# tussenprint.net
KiCad netlist of a schematic drawn in Altium Designer
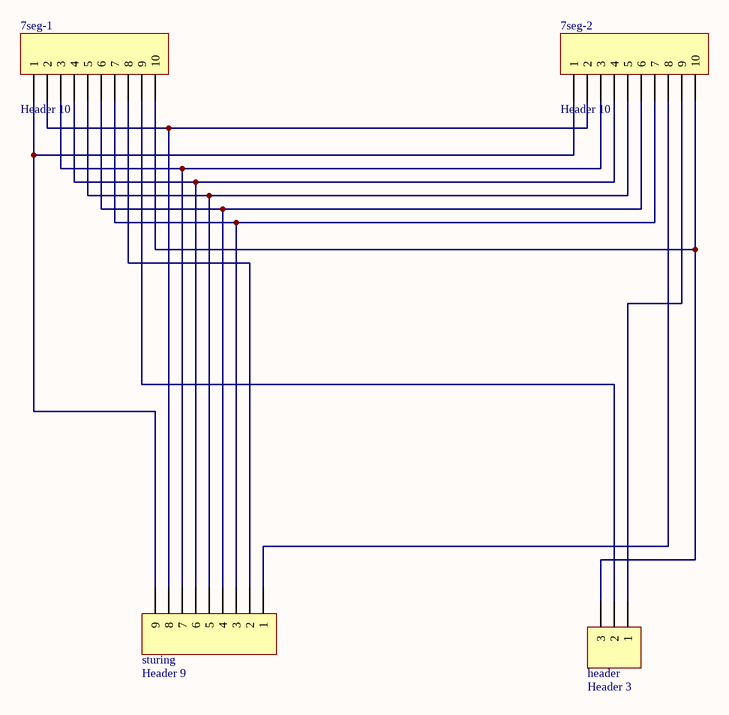
[diagram p0: tussenprint.SchDoc]

(export (version "E")
  (design (tool "Eeschema 10.0.6"))
  (components
    (comp (ref "7seg-1")
      (value "Header 10")
      (footprint "HDR1X10")
      (description "Header, 10-Pin")
      (fields (field (name "PUBLISHER") "Altium Limited"))
      (libsource (lib "Miscellaneous Connectors") (part "Header 10"))
    )
    (comp (ref "7seg-2")
      (value "Header 10")
      (footprint "HDR1X10")
      (description "Header, 10-Pin")
      (fields (field (name "PUBLISHER") "Altium Limited"))
      (libsource (lib "Miscellaneous Connectors") (part "Header 10"))
    )
    (comp (ref "header")
      (value "Header 3")
      (footprint "HDR1X3")
      (description "Header, 3-Pin")
      (fields (field (name "PUBLISHER") "Altium Limited"))
      (libsource (lib "Miscellaneous Connectors") (part "Header 3"))
    )
    (comp (ref "sturing")
      (value "Header 9")
      (footprint "HDR1X9")
      (description "Header, 9-Pin")
      (fields (field (name "PUBLISHER") "Altium Limited"))
      (libsource (lib "Miscellaneous Connectors") (part "Header 9"))
    )
  )
  (nets
    (net (code "1") (name "Net-(7seg-1-Pad1)") (class "Default")
      (node (ref "7seg-1") (pin "1") (pinfunction "1_1") (pintype "passive"))
      (node (ref "7seg-2") (pin "1") (pinfunction "1_1") (pintype "passive"))
      (node (ref "sturing") (pin "9") (pinfunction "9_9") (pintype "passive"))
    )
    (net (code "2") (name "Net-(7seg-1-Pad2)") (class "Default")
      (node (ref "7seg-1") (pin "2") (pinfunction "2_2") (pintype "passive"))
      (node (ref "7seg-2") (pin "2") (pinfunction "2_2") (pintype "passive"))
      (node (ref "sturing") (pin "8") (pinfunction "8_8") (pintype "passive"))
    )
    (net (code "3") (name "Net-(7seg-1-Pad3)") (class "Default")
      (node (ref "7seg-1") (pin "3") (pinfunction "3_3") (pintype "passive"))
      (node (ref "7seg-2") (pin "3") (pinfunction "3_3") (pintype "passive"))
      (node (ref "sturing") (pin "7") (pinfunction "7_7") (pintype "passive"))
    )
    (net (code "4") (name "Net-(7seg-1-Pad4)") (class "Default")
      (node (ref "7seg-1") (pin "4") (pinfunction "4_4") (pintype "passive"))
      (node (ref "7seg-2") (pin "4") (pinfunction "4_4") (pintype "passive"))
      (node (ref "sturing") (pin "6") (pinfunction "6_6") (pintype "passive"))
    )
    (net (code "5") (name "Net-(7seg-1-Pad5)") (class "Default")
      (node (ref "7seg-1") (pin "5") (pinfunction "5_5") (pintype "passive"))
      (node (ref "7seg-2") (pin "5") (pinfunction "5_5") (pintype "passive"))
      (node (ref "sturing") (pin "5") (pinfunction "5_5") (pintype "passive"))
    )
    (net (code "6") (name "Net-(7seg-1-Pad6)") (class "Default")
      (node (ref "7seg-1") (pin "6") (pinfunction "6_6") (pintype "passive"))
      (node (ref "7seg-2") (pin "6") (pinfunction "6_6") (pintype "passive"))
      (node (ref "sturing") (pin "4") (pinfunction "4_4") (pintype "passive"))
    )
    (net (code "7") (name "Net-(7seg-1-Pad7)") (class "Default")
      (node (ref "7seg-1") (pin "7") (pinfunction "7_7") (pintype "passive"))
      (node (ref "7seg-2") (pin "7") (pinfunction "7_7") (pintype "passive"))
      (node (ref "sturing") (pin "3") (pinfunction "3_3") (pintype "passive"))
    )
    (net (code "8") (name "Net-(7seg-1-Pad8)") (class "Default")
      (node (ref "7seg-1") (pin "8") (pinfunction "8_8") (pintype "passive"))
      (node (ref "sturing") (pin "2") (pinfunction "2_2") (pintype "passive"))
    )
    (net (code "9") (name "Net-(7seg-1-Pad9)") (class "Default")
      (node (ref "7seg-1") (pin "9") (pinfunction "9_9") (pintype "passive"))
      (node (ref "header") (pin "2") (pinfunction "2_2") (pintype "passive"))
    )
    (net (code "10") (name "Net-(7seg-1-Pad10)") (class "Default")
      (node (ref "7seg-1") (pin "10") (pinfunction "10_10") (pintype "passive"))
      (node (ref "7seg-2") (pin "10") (pinfunction "10_10") (pintype "passive"))
      (node (ref "header") (pin "3") (pinfunction "3_3") (pintype "passive"))
    )
    (net (code "11") (name "Net-(7seg-2-Pad8)") (class "Default")
      (node (ref "7seg-2") (pin "8") (pinfunction "8_8") (pintype "passive"))
      (node (ref "sturing") (pin "1") (pinfunction "1_1") (pintype "passive"))
    )
    (net (code "12") (name "Net-(7seg-2-Pad9)") (class "Default")
      (node (ref "7seg-2") (pin "9") (pinfunction "9_9") (pintype "passive"))
      (node (ref "header") (pin "1") (pinfunction "1_1") (pintype "passive"))
    )
  )
)
